# Water_Pump_Control_System.net
KiCad netlist of a schematic drawn in EAGLE
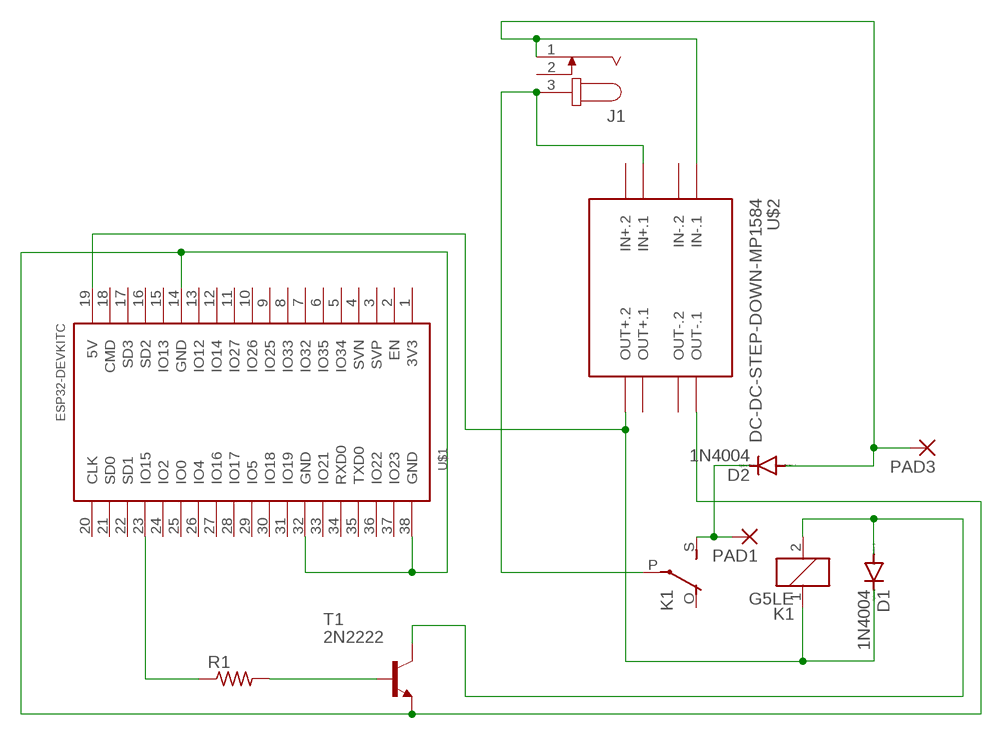
[diagram p0: schematic, sheet 1]

(export (version "E")
  (design (tool "Eeschema 10.0.6"))
  (components
    (comp (ref "D1")
      (value "1N4004")
      (footprint "eagle-import:DO41-10")
      (libsource (lib "eagle-import") (part "1N4004"))
    )
    (comp (ref "D2")
      (value "1N4004")
      (footprint "eagle-import:DO41-10")
      (libsource (lib "eagle-import") (part "1N4004"))
    )
    (comp (ref "J1")
      (value "JACK-PLUG1")
      (footprint "eagle-import:SPC4078")
      (libsource (lib "eagle-import") (part "JACK-PLUG1"))
    )
    (comp (ref "K1")
      (value "G5LE")
      (footprint "eagle-import:G5LE")
      (libsource (lib "eagle-import") (part "G5LE"))
    )
    (comp (ref "PAD1")
      (value "1,6/0,8")
      (footprint "eagle-import:1,6_0,8")
      (libsource (lib "eagle-import") (part "1,6/0,8"))
    )
    (comp (ref "PAD3")
      (value "1,6/0,8")
      (footprint "eagle-import:1,6_0,8")
      (libsource (lib "eagle-import") (part "1,6/0,8"))
    )
    (comp (ref "R1")
      (value "R-US_0207/10")
      (footprint "eagle-import:0207_10")
      (libsource (lib "eagle-import") (part "R-US_0207/10"))
    )
    (comp (ref "T1")
      (value "2N2222")
      (footprint "eagle-import:TO92-EBC-OVAL")
      (libsource (lib "eagle-import") (part "2N2222"))
    )
    (comp (ref "U$1")
      (value "ESP32DEVKITC")
      (footprint "eagle-import:ESP32-DEVKITC")
      (libsource (lib "eagle-import") (part "ESP32DEVKITC"))
    )
    (comp (ref "U$2")
      (value "DC-DC-STEP-DOWN-MP1584")
      (footprint "eagle-import:DC-DC-STEP-DOWN-MP1584")
      (libsource (lib "eagle-import") (part "DC-DC-STEP-DOWN-MP1584"))
    )
  )
  (nets
    (net (code "1") (name "Net-(D1-PadA)") (class "Default")
      (node (ref "D1") (pin "A") (pinfunction "A_A") (pintype "passive"))
      (node (ref "K1") (pin "2") (pinfunction "2_2") (pintype "passive"))
      (node (ref "T1") (pin "C") (pinfunction "C_C") (pintype "passive"))
    )
    (net (code "2") (name "Net-(J1-Pad3)") (class "Default")
      (node (ref "J1") (pin "3") (pinfunction "3_3") (pintype "passive"))
      (node (ref "K1") (pin "P") (pinfunction "P_P") (pintype "passive"))
      (node (ref "U$2") (pin "IN+.1") (pinfunction "IN+.1_IN+.1") (pintype "bidirectional"))
    )
    (net (code "3") (name "Net-(PAD1-P)") (class "Default")
      (node (ref "D2") (pin "C") (pinfunction "C_C") (pintype "passive"))
      (node (ref "K1") (pin "S") (pinfunction "S_S") (pintype "passive"))
      (node (ref "PAD1") (pin "1") (pinfunction "P_1") (pintype "passive"))
    )
    (net (code "4") (name "Net-(PAD3-P)") (class "Default")
      (node (ref "D2") (pin "A") (pinfunction "A_A") (pintype "passive"))
      (node (ref "J1") (pin "1") (pinfunction "1_1") (pintype "passive"))
      (node (ref "PAD3") (pin "1") (pinfunction "P_1") (pintype "passive"))
      (node (ref "U$2") (pin "IN-.1") (pinfunction "IN-.1_IN-.1") (pintype "bidirectional"))
    )
    (net (code "5") (name "Net-(R1-Pad2)") (class "Default")
      (node (ref "R1") (pin "2") (pinfunction "2_2") (pintype "passive"))
      (node (ref "T1") (pin "B") (pinfunction "B_B") (pintype "passive"))
    )
    (net (code "6") (name "Net-(T1-PadE)") (class "Default")
      (node (ref "T1") (pin "E") (pinfunction "E_E") (pintype "passive"))
      (node (ref "U$1") (pin "14") (pinfunction "GND_14") (pintype "bidirectional"))
      (node (ref "U$1") (pin "32") (pinfunction "GND_32") (pintype "bidirectional"))
      (node (ref "U$1") (pin "38") (pinfunction "GND_38") (pintype "bidirectional"))
      (node (ref "U$2") (pin "OUT-.1") (pinfunction "OUT-.1_OUT-.1") (pintype "bidirectional"))
    )
    (net (code "7") (name "Net-(U$1-5V)") (class "Default")
      (node (ref "D1") (pin "C") (pinfunction "C_C") (pintype "passive"))
      (node (ref "K1") (pin "1") (pinfunction "1_1") (pintype "passive"))
      (node (ref "U$1") (pin "19") (pinfunction "5V_19") (pintype "bidirectional"))
      (node (ref "U$2") (pin "OUT+.2") (pinfunction "OUT+.2_OUT+.2") (pintype "bidirectional"))
    )
    (net (code "8") (name "Net-(U$1-IO15)") (class "Default")
      (node (ref "R1") (pin "1") (pinfunction "1_1") (pintype "passive"))
      (node (ref "U$1") (pin "23") (pinfunction "IO15_23") (pintype "bidirectional"))
    )
    (net (code "9") (name "unconnected-(J1-Pad2)") (class "Default")
      (node (ref "J1") (pin "2") (pinfunction "2_2") (pintype "passive"))
    )
    (net (code "10") (name "unconnected-(K1-PadO)") (class "Default")
      (node (ref "K1") (pin "O") (pinfunction "O_O") (pintype "passive"))
    )
    (net (code "11") (name "unconnected-(U$1-3V3-Pad1)") (class "Default")
      (node (ref "U$1") (pin "1") (pinfunction "3V3_1") (pintype "bidirectional"))
    )
    (net (code "12") (name "unconnected-(U$1-CLK-Pad20)") (class "Default")
      (node (ref "U$1") (pin "20") (pinfunction "CLK_20") (pintype "bidirectional"))
    )
    (net (code "13") (name "unconnected-(U$1-CMD-Pad18)") (class "Default")
      (node (ref "U$1") (pin "18") (pinfunction "CMD_18") (pintype "bidirectional"))
    )
    (net (code "14") (name "unconnected-(U$1-EN-Pad2)") (class "Default")
      (node (ref "U$1") (pin "2") (pinfunction "EN_2") (pintype "bidirectional"))
    )
    (net (code "15") (name "unconnected-(U$1-IO0-Pad25)") (class "Default")
      (node (ref "U$1") (pin "25") (pinfunction "IO0_25") (pintype "bidirectional"))
    )
    (net (code "16") (name "unconnected-(U$1-IO2-Pad24)") (class "Default")
      (node (ref "U$1") (pin "24") (pinfunction "IO2_24") (pintype "bidirectional"))
    )
    (net (code "17") (name "unconnected-(U$1-IO4-Pad26)") (class "Default")
      (node (ref "U$1") (pin "26") (pinfunction "IO4_26") (pintype "bidirectional"))
    )
    (net (code "18") (name "unconnected-(U$1-IO5-Pad29)") (class "Default")
      (node (ref "U$1") (pin "29") (pinfunction "IO5_29") (pintype "bidirectional"))
    )
    (net (code "19") (name "unconnected-(U$1-IO12-Pad13)") (class "Default")
      (node (ref "U$1") (pin "13") (pinfunction "IO12_13") (pintype "bidirectional"))
    )
    (net (code "20") (name "unconnected-(U$1-IO13-Pad15)") (class "Default")
      (node (ref "U$1") (pin "15") (pinfunction "IO13_15") (pintype "bidirectional"))
    )
    (net (code "21") (name "unconnected-(U$1-IO14-Pad12)") (class "Default")
      (node (ref "U$1") (pin "12") (pinfunction "IO14_12") (pintype "bidirectional"))
    )
    (net (code "22") (name "unconnected-(U$1-IO16-Pad27)") (class "Default")
      (node (ref "U$1") (pin "27") (pinfunction "IO16_27") (pintype "bidirectional"))
    )
    (net (code "23") (name "unconnected-(U$1-IO17-Pad28)") (class "Default")
      (node (ref "U$1") (pin "28") (pinfunction "IO17_28") (pintype "bidirectional"))
    )
    (net (code "24") (name "unconnected-(U$1-IO18-Pad30)") (class "Default")
      (node (ref "U$1") (pin "30") (pinfunction "IO18_30") (pintype "bidirectional"))
    )
    (net (code "25") (name "unconnected-(U$1-IO19-Pad31)") (class "Default")
      (node (ref "U$1") (pin "31") (pinfunction "IO19_31") (pintype "bidirectional"))
    )
    (net (code "26") (name "unconnected-(U$1-IO21-Pad33)") (class "Default")
      (node (ref "U$1") (pin "33") (pinfunction "IO21_33") (pintype "bidirectional"))
    )
    (net (code "27") (name "unconnected-(U$1-IO22-Pad36)") (class "Default")
      (node (ref "U$1") (pin "36") (pinfunction "IO22_36") (pintype "bidirectional"))
    )
    (net (code "28") (name "unconnected-(U$1-IO23-Pad37)") (class "Default")
      (node (ref "U$1") (pin "37") (pinfunction "IO23_37") (pintype "bidirectional"))
    )
    (net (code "29") (name "unconnected-(U$1-IO25-Pad9)") (class "Default")
      (node (ref "U$1") (pin "9") (pinfunction "IO25_9") (pintype "bidirectional"))
    )
    (net (code "30") (name "unconnected-(U$1-IO26-Pad10)") (class "Default")
      (node (ref "U$1") (pin "10") (pinfunction "IO26_10") (pintype "bidirectional"))
    )
    (net (code "31") (name "unconnected-(U$1-IO27-Pad11)") (class "Default")
      (node (ref "U$1") (pin "11") (pinfunction "IO27_11") (pintype "bidirectional"))
    )
    (net (code "32") (name "unconnected-(U$1-IO32-Pad7)") (class "Default")
      (node (ref "U$1") (pin "7") (pinfunction "IO32_7") (pintype "bidirectional"))
    )
    (net (code "33") (name "unconnected-(U$1-IO33-Pad8)") (class "Default")
      (node (ref "U$1") (pin "8") (pinfunction "IO33_8") (pintype "bidirectional"))
    )
    (net (code "34") (name "unconnected-(U$1-IO34-Pad5)") (class "Default")
      (node (ref "U$1") (pin "5") (pinfunction "IO34_5") (pintype "bidirectional"))
    )
    (net (code "35") (name "unconnected-(U$1-IO35-Pad6)") (class "Default")
      (node (ref "U$1") (pin "6") (pinfunction "IO35_6") (pintype "bidirectional"))
    )
    (net (code "36") (name "unconnected-(U$1-RXD0-Pad34)") (class "Default")
      (node (ref "U$1") (pin "34") (pinfunction "RXD0_34") (pintype "bidirectional"))
    )
    (net (code "37") (name "unconnected-(U$1-SD0-Pad21)") (class "Default")
      (node (ref "U$1") (pin "21") (pinfunction "SD0_21") (pintype "bidirectional"))
    )
    (net (code "38") (name "unconnected-(U$1-SD1-Pad22)") (class "Default")
      (node (ref "U$1") (pin "22") (pinfunction "SD1_22") (pintype "bidirectional"))
    )
    (net (code "39") (name "unconnected-(U$1-SD2-Pad16)") (class "Default")
      (node (ref "U$1") (pin "16") (pinfunction "SD2_16") (pintype "bidirectional"))
    )
    (net (code "40") (name "unconnected-(U$1-SD3-Pad17)") (class "Default")
      (node (ref "U$1") (pin "17") (pinfunction "SD3_17") (pintype "bidirectional"))
    )
    (net (code "41") (name "unconnected-(U$1-SVN-Pad4)") (class "Default")
      (node (ref "U$1") (pin "4") (pinfunction "SVN_4") (pintype "bidirectional"))
    )
    (net (code "42") (name "unconnected-(U$1-SVP-Pad3)") (class "Default")
      (node (ref "U$1") (pin "3") (pinfunction "SVP_3") (pintype "bidirectional"))
    )
    (net (code "43") (name "unconnected-(U$1-TXD0-Pad35)") (class "Default")
      (node (ref "U$1") (pin "35") (pinfunction "TXD0_35") (pintype "bidirectional"))
    )
    (net (code "44") (name "unconnected-(U$2-PadIN+.2)") (class "Default")
      (node (ref "U$2") (pin "IN+.2") (pinfunction "IN+.2_IN+.2") (pintype "bidirectional"))
    )
    (net (code "45") (name "unconnected-(U$2-PadIN-.2)") (class "Default")
      (node (ref "U$2") (pin "IN-.2") (pinfunction "IN-.2_IN-.2") (pintype "bidirectional"))
    )
    (net (code "46") (name "unconnected-(U$2-PadOUT+.1)") (class "Default")
      (node (ref "U$2") (pin "OUT+.1") (pinfunction "OUT+.1_OUT+.1") (pintype "bidirectional"))
    )
    (net (code "47") (name "unconnected-(U$2-PadOUT-.2)") (class "Default")
      (node (ref "U$2") (pin "OUT-.2") (pinfunction "OUT-.2_OUT-.2") (pintype "bidirectional"))
    )
  )
)
